# isolated-analog-interface-hw.net
KiCad netlist of a schematic drawn in Altium Designer
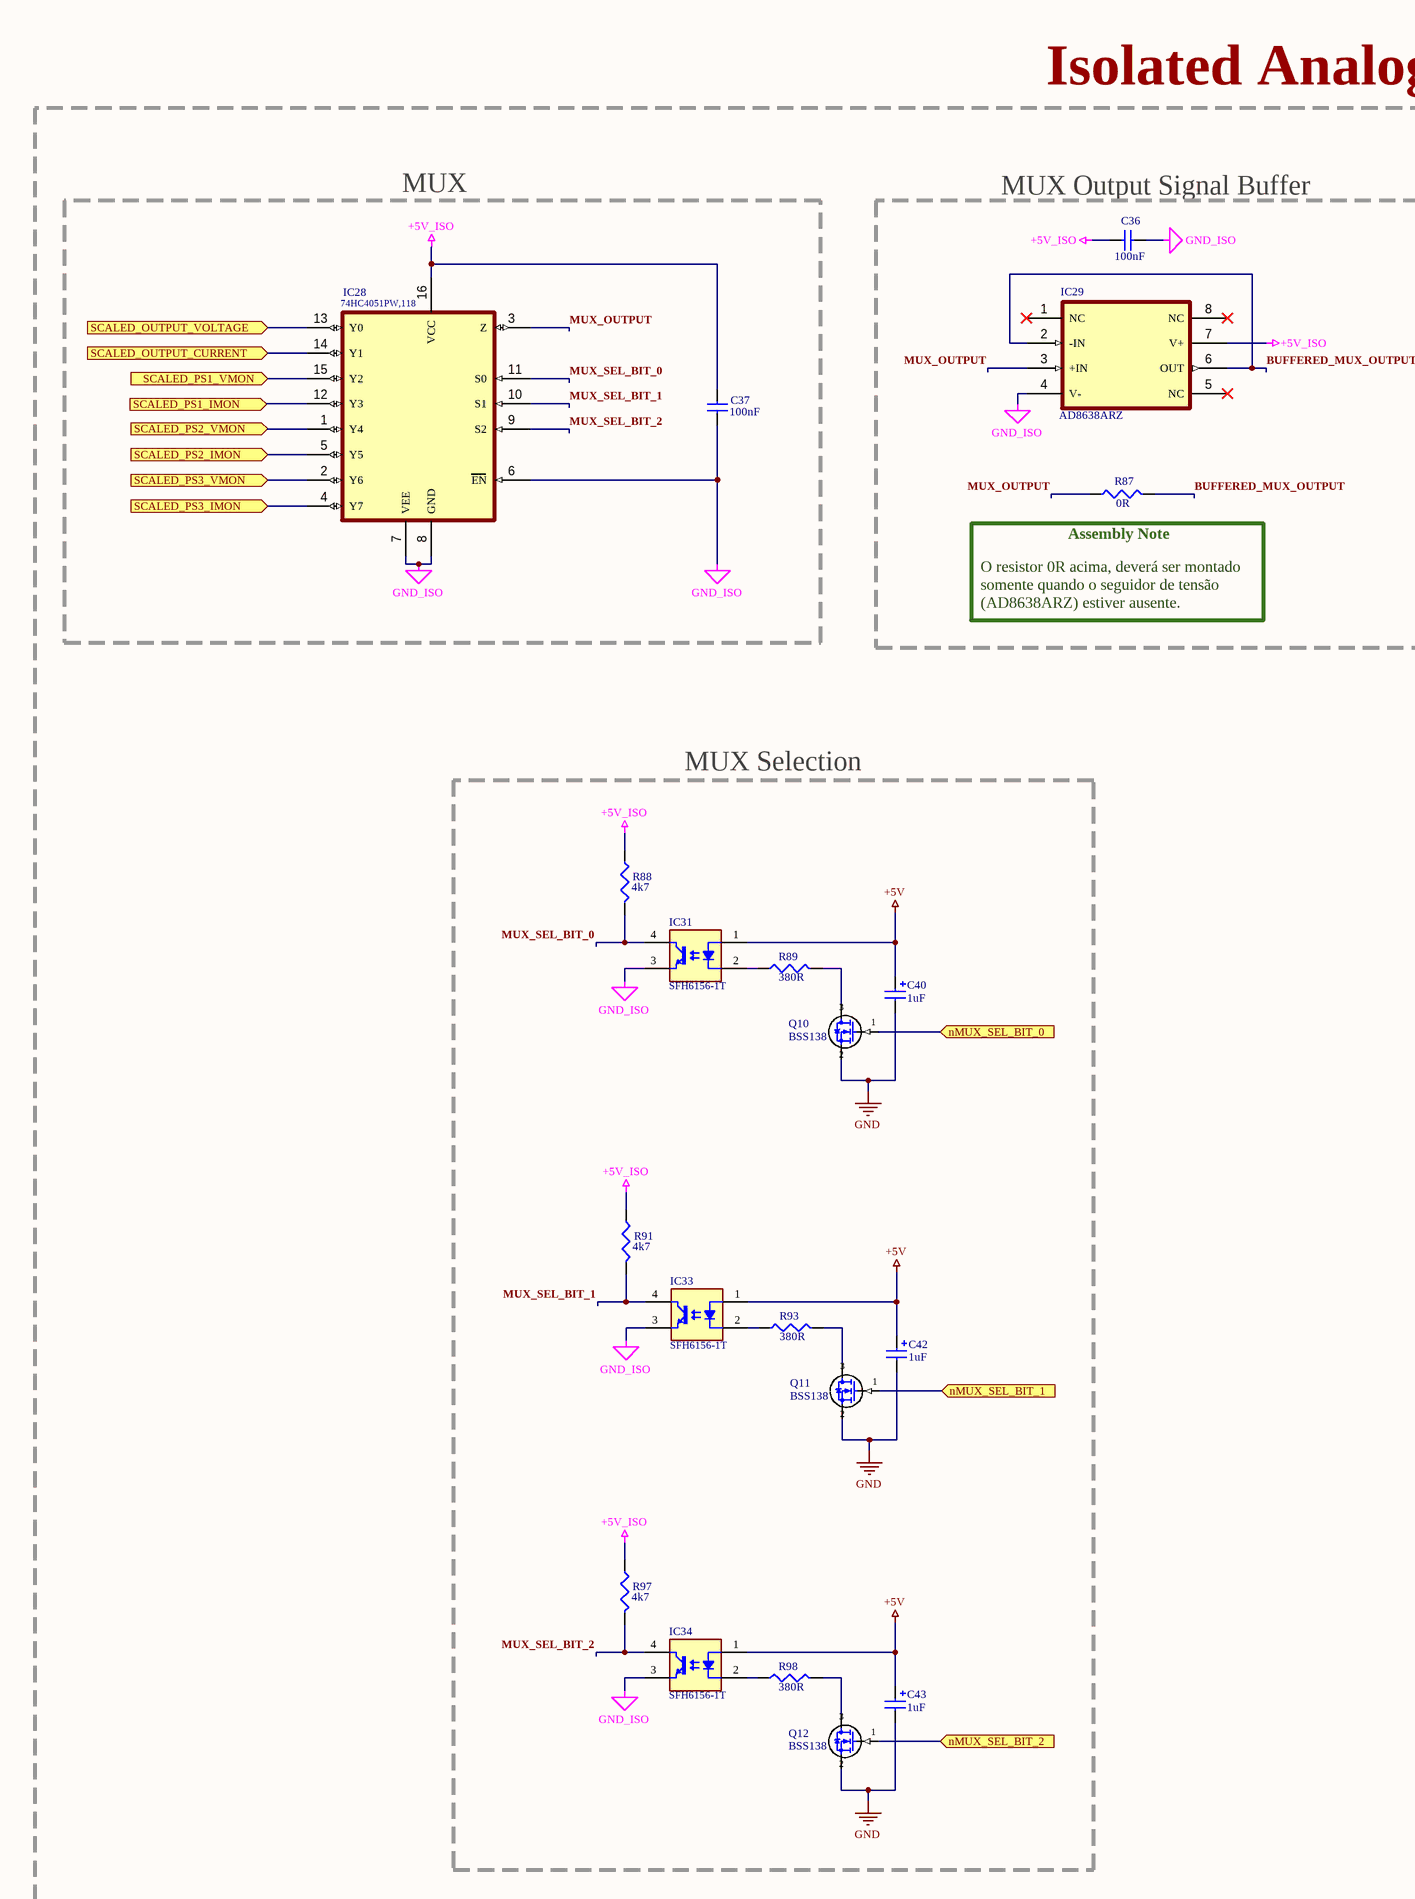
[diagram p0: isolated-analog-interface-hw.SchDoc, left]
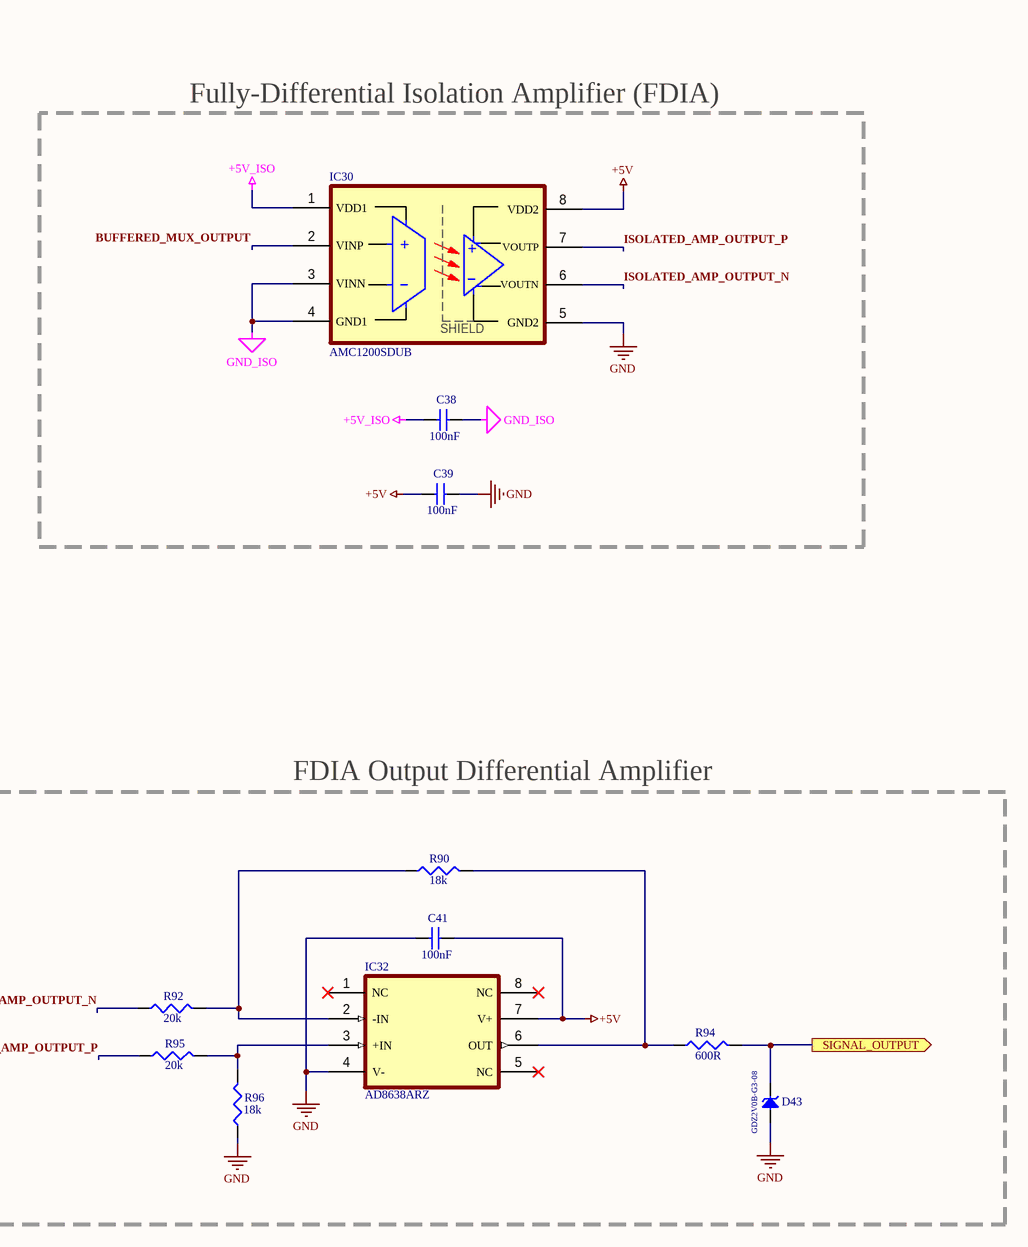
[diagram p1: isolated-analog-interface-hw.SchDoc, right]

(export (version "E")
  (design (tool "Eeschema 10.0.6"))
  (components
    (comp (ref "C36")
      (value "100nF")
      (footprint "C0805")
      (libsource (lib "acopians-powerspy-monitoring-hw-library-schematic") (part "Capacitor 100nF"))
    )
    (comp (ref "C37")
      (value "100nF")
      (footprint "C0805")
      (libsource (lib "acopians-powerspy-monitoring-hw-library-schematic") (part "Capacitor 100nF"))
    )
    (comp (ref "C38")
      (value "100nF")
      (footprint "C0805")
      (libsource (lib "acopians-powerspy-monitoring-hw-library-schematic") (part "Capacitor 100nF"))
    )
    (comp (ref "C39")
      (value "100nF")
      (footprint "C0805")
      (libsource (lib "acopians-powerspy-monitoring-hw-library-schematic") (part "Capacitor 100nF"))
    )
    (comp (ref "C40")
      (value "1uF")
      (footprint "C1206")
      (libsource (lib "acopians-powerspy-monitoring-hw-library-schematic") (part "Capacitor 1uF"))
    )
    (comp (ref "C41")
      (value "100nF")
      (footprint "C0805")
      (libsource (lib "acopians-powerspy-monitoring-hw-library-schematic") (part "Capacitor 100nF"))
    )
    (comp (ref "C42")
      (value "1uF")
      (footprint "C1206")
      (libsource (lib "acopians-powerspy-monitoring-hw-library-schematic") (part "Capacitor 1uF"))
    )
    (comp (ref "C43")
      (value "1uF")
      (footprint "C1206")
      (libsource (lib "acopians-powerspy-monitoring-hw-library-schematic") (part "Capacitor 1uF"))
    )
    (comp (ref "D43")
      (value "GDZ2V0B-G3-08")
      (footprint "SOD-323")
      (libsource (lib "acopians-powerspy-monitoring-hw-library-schematic") (part "Zener GDZ2V0B-G3-08"))
    )
    (comp (ref "IC28")
      (value "74HC4051PW,118")
      (footprint "TSSOP-16")
      (description "8-channel analog multiplexer, TSSOP-16")
      (libsource (lib "acopians-powerspy-monitoring-hw-library-schematic") (part "74HC4051PW,118"))
    )
    (comp (ref "IC29")
      (value "AD8638ARZ")
      (footprint "SOIC-8")
      (description "16V, Auto-Zero, Rail-to-Rail Output Operational Amplifiers")
      (libsource (lib "acopians-powerspy-monitoring-hw-library-schematic") (part "AD8638ARZ"))
    )
    (comp (ref "IC30")
      (value "AMC1200SDUB")
      (footprint "SOP-8")
      (description "Fully-Differential Isolation Amplifier")
      (libsource (lib "acopians-powerspy-monitoring-hw-library-schematic") (part "AMC1200SDUB"))
    )
    (comp (ref "IC31")
      (value "SFH6156-1T")
      (footprint "SMD-4")
      (description "Optocoupler 1 Channel, Phototransistor Output, SMD-4")
      (libsource (lib "acopians-powerspy-monitoring-hw-library-schematic") (part "SFH6156-1T"))
    )
    (comp (ref "IC32")
      (value "AD8638ARZ")
      (footprint "SOIC-8")
      (description "16V, Auto-Zero, Rail-to-Rail Output Operational Amplifiers")
      (libsource (lib "acopians-powerspy-monitoring-hw-library-schematic") (part "AD8638ARZ"))
    )
    (comp (ref "IC33")
      (value "SFH6156-1T")
      (footprint "SMD-4")
      (description "Optocoupler 1 Channel, Phototransistor Output, SMD-4")
      (libsource (lib "acopians-powerspy-monitoring-hw-library-schematic") (part "SFH6156-1T"))
    )
    (comp (ref "IC34")
      (value "SFH6156-1T")
      (footprint "SMD-4")
      (description "Optocoupler 1 Channel, Phototransistor Output, SMD-4")
      (libsource (lib "acopians-powerspy-monitoring-hw-library-schematic") (part "SFH6156-1T"))
    )
    (comp (ref "Q10")
      (value "BSS138")
      (footprint "SOT_23_3")
      (description "MOSFET N-Channel")
      (libsource (lib "acopians-powerspy-monitoring-hw-library-schematic") (part "BSS138"))
    )
    (comp (ref "Q11")
      (value "BSS138")
      (footprint "SOT_23_3")
      (description "MOSFET N-Channel")
      (libsource (lib "acopians-powerspy-monitoring-hw-library-schematic") (part "BSS138"))
    )
    (comp (ref "Q12")
      (value "BSS138")
      (footprint "SOT_23_3")
      (description "MOSFET N-Channel")
      (libsource (lib "acopians-powerspy-monitoring-hw-library-schematic") (part "BSS138"))
    )
    (comp (ref "R87")
      (value "0R")
      (footprint "Resistor 0805")
      (description "Size 0805")
      (libsource (lib "acopians-powerspy-monitoring-hw-library-schematic") (part "Resistor 0R - 0805"))
    )
    (comp (ref "R88")
      (value "4k7")
      (footprint "Resistor 0805")
      (description "Size 0805")
      (libsource (lib "acopians-powerspy-monitoring-hw-library-schematic") (part "Resistor 4k7"))
    )
    (comp (ref "R89")
      (value "380R")
      (footprint "Resistor 0805")
      (description "Size 0805")
      (libsource (lib "acopians-powerspy-monitoring-hw-library-schematic") (part "Resistor 380R"))
    )
    (comp (ref "R90")
      (value "18k")
      (footprint "Resistor 0805")
      (libsource (lib "acopians-powerspy-monitoring-hw-library-schematic") (part "Resistor 18k"))
    )
    (comp (ref "R91")
      (value "4k7")
      (footprint "Resistor 0805")
      (description "Size 0805")
      (libsource (lib "acopians-powerspy-monitoring-hw-library-schematic") (part "Resistor 4k7"))
    )
    (comp (ref "R92")
      (value "20k")
      (footprint "Resistor 0805")
      (libsource (lib "acopians-powerspy-monitoring-hw-library-schematic") (part "Resistor 20k"))
    )
    (comp (ref "R93")
      (value "380R")
      (footprint "Resistor 0805")
      (description "Size 0805")
      (libsource (lib "acopians-powerspy-monitoring-hw-library-schematic") (part "Resistor 380R"))
    )
    (comp (ref "R94")
      (value "600R")
      (footprint "Resistor 0805")
      (libsource (lib "acopians-powerspy-monitoring-hw-library-schematic") (part "Resistor 600R"))
    )
    (comp (ref "R95")
      (value "20k")
      (footprint "Resistor 0805")
      (libsource (lib "acopians-powerspy-monitoring-hw-library-schematic") (part "Resistor 20k"))
    )
    (comp (ref "R96")
      (value "18k")
      (footprint "Resistor 0805")
      (libsource (lib "acopians-powerspy-monitoring-hw-library-schematic") (part "Resistor 18k"))
    )
    (comp (ref "R97")
      (value "4k7")
      (footprint "Resistor 0805")
      (description "Size 0805")
      (libsource (lib "acopians-powerspy-monitoring-hw-library-schematic") (part "Resistor 4k7"))
    )
    (comp (ref "R98")
      (value "380R")
      (footprint "Resistor 0805")
      (description "Size 0805")
      (libsource (lib "acopians-powerspy-monitoring-hw-library-schematic") (part "Resistor 380R"))
    )
  )
  (nets
    (net (code "1") (name "+5V") (class "Default")
      (node (ref "C39") (pin "1") (pinfunction "1_1") (pintype "passive"))
      (node (ref "C40") (pin "1") (pinfunction "1_1") (pintype "passive"))
      (node (ref "C41") (pin "2") (pinfunction "2_2") (pintype "passive"))
      (node (ref "C42") (pin "1") (pinfunction "1_1") (pintype "passive"))
      (node (ref "C43") (pin "1") (pinfunction "1_1") (pintype "passive"))
      (node (ref "IC30") (pin "8") (pinfunction "VDD2_8") (pintype "passive"))
      (node (ref "IC31") (pin "1") (pinfunction "A_1") (pintype "passive"))
      (node (ref "IC32") (pin "7") (pinfunction "V+_7") (pintype "passive"))
      (node (ref "IC33") (pin "1") (pinfunction "A_1") (pintype "passive"))
      (node (ref "IC34") (pin "1") (pinfunction "A_1") (pintype "passive"))
    )
    (net (code "2") (name "+5V_ISO") (class "Default")
      (node (ref "C36") (pin "1") (pinfunction "1_1") (pintype "passive"))
      (node (ref "C37") (pin "1") (pinfunction "1_1") (pintype "passive"))
      (node (ref "C38") (pin "1") (pinfunction "1_1") (pintype "passive"))
      (node (ref "IC28") (pin "16") (pinfunction "VCC_16") (pintype "passive"))
      (node (ref "IC29") (pin "7") (pinfunction "V+_7") (pintype "passive"))
      (node (ref "IC30") (pin "1") (pinfunction "VDD1_1") (pintype "passive"))
      (node (ref "R88") (pin "1") (pinfunction "1_1") (pintype "passive"))
      (node (ref "R91") (pin "1") (pinfunction "1_1") (pintype "passive"))
      (node (ref "R97") (pin "1") (pinfunction "1_1") (pintype "passive"))
    )
    (net (code "3") (name "/BUFFERED_MUX_OUTPUT") (class "Default")
      (node (ref "IC29") (pin "2") (pinfunction "-IN_2") (pintype "input"))
      (node (ref "IC29") (pin "6") (pinfunction "OUT_6") (pintype "output"))
      (node (ref "IC30") (pin "2") (pinfunction "VINP_2") (pintype "passive"))
      (node (ref "R87") (pin "2") (pinfunction "2_2") (pintype "passive"))
    )
    (net (code "4") (name "/ISOLATED_AMP_OUTPUT_N") (class "Default")
      (node (ref "IC30") (pin "6") (pinfunction "VOUTN_6") (pintype "passive"))
      (node (ref "R92") (pin "1") (pinfunction "1_1") (pintype "passive"))
    )
    (net (code "5") (name "/ISOLATED_AMP_OUTPUT_P") (class "Default")
      (node (ref "IC30") (pin "7") (pinfunction "VOUTP_7") (pintype "passive"))
      (node (ref "R95") (pin "1") (pinfunction "1_1") (pintype "passive"))
    )
    (net (code "6") (name "/MUX_OUTPUT") (class "Default")
      (node (ref "IC28") (pin "3") (pinfunction "Z_3") (pintype "bidirectional"))
      (node (ref "IC29") (pin "3") (pinfunction "+IN_3") (pintype "input"))
      (node (ref "R87") (pin "1") (pinfunction "1_1") (pintype "passive"))
    )
    (net (code "7") (name "/MUX_SEL_BIT_0") (class "Default")
      (node (ref "IC28") (pin "11") (pinfunction "S0_11") (pintype "input"))
      (node (ref "IC31") (pin "4") (pinfunction "C_4") (pintype "open_collector"))
      (node (ref "R88") (pin "2") (pinfunction "2_2") (pintype "passive"))
    )
    (net (code "8") (name "/MUX_SEL_BIT_1") (class "Default")
      (node (ref "IC28") (pin "10") (pinfunction "S1_10") (pintype "input"))
      (node (ref "IC33") (pin "4") (pinfunction "C_4") (pintype "open_collector"))
      (node (ref "R91") (pin "2") (pinfunction "2_2") (pintype "passive"))
    )
    (net (code "9") (name "/MUX_SEL_BIT_2") (class "Default")
      (node (ref "IC28") (pin "9") (pinfunction "S2_9") (pintype "input"))
      (node (ref "IC34") (pin "4") (pinfunction "C_4") (pintype "open_collector"))
      (node (ref "R97") (pin "2") (pinfunction "2_2") (pintype "passive"))
    )
    (net (code "10") (name "/SCALED_OUTPUT_CURRENT") (class "Default")
      (node (ref "IC28") (pin "14") (pinfunction "Y1_14") (pintype "bidirectional"))
    )
    (net (code "11") (name "/SCALED_OUTPUT_VOLTAGE") (class "Default")
      (node (ref "IC28") (pin "13") (pinfunction "Y0_13") (pintype "bidirectional"))
    )
    (net (code "12") (name "/SCALED_PS1_IMON") (class "Default")
      (node (ref "IC28") (pin "12") (pinfunction "Y3_12") (pintype "bidirectional"))
    )
    (net (code "13") (name "/SCALED_PS1_VMON") (class "Default")
      (node (ref "IC28") (pin "15") (pinfunction "Y2_15") (pintype "bidirectional"))
    )
    (net (code "14") (name "/SCALED_PS2_IMON") (class "Default")
      (node (ref "IC28") (pin "5") (pinfunction "Y5_5") (pintype "bidirectional"))
    )
    (net (code "15") (name "/SCALED_PS2_VMON") (class "Default")
      (node (ref "IC28") (pin "1") (pinfunction "Y4_1") (pintype "bidirectional"))
    )
    (net (code "16") (name "/SCALED_PS3_IMON") (class "Default")
      (node (ref "IC28") (pin "4") (pinfunction "Y7_4") (pintype "bidirectional"))
    )
    (net (code "17") (name "/SCALED_PS3_VMON") (class "Default")
      (node (ref "IC28") (pin "2") (pinfunction "Y6_2") (pintype "bidirectional"))
    )
    (net (code "18") (name "/SIGNAL_OUTPUT") (class "Default")
      (node (ref "D43") (pin "2") (pintype "passive"))
      (node (ref "R94") (pin "2") (pinfunction "2_2") (pintype "passive"))
    )
    (net (code "19") (name "/nMUX_SEL_BIT_0") (class "Default")
      (node (ref "Q10") (pin "1") (pinfunction "G_1") (pintype "input"))
    )
    (net (code "20") (name "/nMUX_SEL_BIT_1") (class "Default")
      (node (ref "Q11") (pin "1") (pinfunction "G_1") (pintype "input"))
    )
    (net (code "21") (name "/nMUX_SEL_BIT_2") (class "Default")
      (node (ref "Q12") (pin "1") (pinfunction "G_1") (pintype "input"))
    )
    (net (code "22") (name "GND") (class "Default")
      (node (ref "C39") (pin "2") (pinfunction "2_2") (pintype "passive"))
      (node (ref "C40") (pin "2") (pinfunction "2_2") (pintype "passive"))
      (node (ref "C41") (pin "1") (pinfunction "1_1") (pintype "passive"))
      (node (ref "C42") (pin "2") (pinfunction "2_2") (pintype "passive"))
      (node (ref "C43") (pin "2") (pinfunction "2_2") (pintype "passive"))
      (node (ref "D43") (pin "1") (pintype "passive"))
      (node (ref "IC30") (pin "5") (pinfunction "GND2_5") (pintype "passive"))
      (node (ref "IC32") (pin "4") (pinfunction "V-_4") (pintype "passive"))
      (node (ref "Q10") (pin "2") (pinfunction "S_2") (pintype "passive"))
      (node (ref "Q11") (pin "2") (pinfunction "S_2") (pintype "passive"))
      (node (ref "Q12") (pin "2") (pinfunction "S_2") (pintype "passive"))
      (node (ref "R96") (pin "1") (pinfunction "1_1") (pintype "passive"))
    )
    (net (code "23") (name "GND_ISO") (class "Default")
      (node (ref "C36") (pin "2") (pinfunction "2_2") (pintype "passive"))
      (node (ref "C37") (pin "2") (pinfunction "2_2") (pintype "passive"))
      (node (ref "C38") (pin "2") (pinfunction "2_2") (pintype "passive"))
      (node (ref "IC28") (pin "6") (pinfunction "EN_6") (pintype "input"))
      (node (ref "IC28") (pin "7") (pinfunction "VEE_7") (pintype "passive"))
      (node (ref "IC28") (pin "8") (pinfunction "GND_8") (pintype "passive"))
      (node (ref "IC29") (pin "4") (pinfunction "V-_4") (pintype "passive"))
      (node (ref "IC30") (pin "3") (pinfunction "VINN_3") (pintype "passive"))
      (node (ref "IC30") (pin "4") (pinfunction "GND1_4") (pintype "passive"))
      (node (ref "IC31") (pin "3") (pinfunction "E_3") (pintype "open_emitter"))
      (node (ref "IC33") (pin "3") (pinfunction "E_3") (pintype "open_emitter"))
      (node (ref "IC34") (pin "3") (pinfunction "E_3") (pintype "open_emitter"))
    )
    (net (code "24") (name "Net-(IC31-C-Pad2)") (class "Default")
      (node (ref "IC31") (pin "2") (pinfunction "C_2") (pintype "passive"))
      (node (ref "R89") (pin "1") (pinfunction "1_1") (pintype "passive"))
    )
    (net (code "25") (name "Net-(IC32-+IN)") (class "Default")
      (node (ref "IC32") (pin "3") (pinfunction "+IN_3") (pintype "input"))
      (node (ref "R95") (pin "2") (pinfunction "2_2") (pintype "passive"))
      (node (ref "R96") (pin "2") (pinfunction "2_2") (pintype "passive"))
    )
    (net (code "26") (name "Net-(IC32--IN)") (class "Default")
      (node (ref "IC32") (pin "2") (pinfunction "-IN_2") (pintype "input"))
      (node (ref "R90") (pin "1") (pinfunction "1_1") (pintype "passive"))
      (node (ref "R92") (pin "2") (pinfunction "2_2") (pintype "passive"))
    )
    (net (code "27") (name "Net-(IC32-OUT)") (class "Default")
      (node (ref "IC32") (pin "6") (pinfunction "OUT_6") (pintype "output"))
      (node (ref "R90") (pin "2") (pinfunction "2_2") (pintype "passive"))
      (node (ref "R94") (pin "1") (pinfunction "1_1") (pintype "passive"))
    )
    (net (code "28") (name "Net-(IC33-C-Pad2)") (class "Default")
      (node (ref "IC33") (pin "2") (pinfunction "C_2") (pintype "passive"))
      (node (ref "R93") (pin "1") (pinfunction "1_1") (pintype "passive"))
    )
    (net (code "29") (name "Net-(IC34-C-Pad2)") (class "Default")
      (node (ref "IC34") (pin "2") (pinfunction "C_2") (pintype "passive"))
      (node (ref "R98") (pin "1") (pinfunction "1_1") (pintype "passive"))
    )
    (net (code "30") (name "Net-(Q10-D)") (class "Default")
      (node (ref "Q10") (pin "3") (pinfunction "D_3") (pintype "passive"))
      (node (ref "R89") (pin "2") (pinfunction "2_2") (pintype "passive"))
    )
    (net (code "31") (name "Net-(Q11-D)") (class "Default")
      (node (ref "Q11") (pin "3") (pinfunction "D_3") (pintype "passive"))
      (node (ref "R93") (pin "2") (pinfunction "2_2") (pintype "passive"))
    )
    (net (code "32") (name "Net-(Q12-D)") (class "Default")
      (node (ref "Q12") (pin "3") (pinfunction "D_3") (pintype "passive"))
      (node (ref "R98") (pin "2") (pinfunction "2_2") (pintype "passive"))
    )
    (net (code "33") (name "unconnected-(IC29-NC-Pad1)") (class "Default")
      (node (ref "IC29") (pin "1") (pinfunction "NC_1") (pintype "passive+no_connect"))
    )
    (net (code "34") (name "unconnected-(IC29-NC-Pad5)") (class "Default")
      (node (ref "IC29") (pin "5") (pinfunction "NC_5") (pintype "passive+no_connect"))
    )
    (net (code "35") (name "unconnected-(IC29-NC-Pad8)") (class "Default")
      (node (ref "IC29") (pin "8") (pinfunction "NC_8") (pintype "passive+no_connect"))
    )
    (net (code "36") (name "unconnected-(IC32-NC-Pad1)") (class "Default")
      (node (ref "IC32") (pin "1") (pinfunction "NC_1") (pintype "passive+no_connect"))
    )
    (net (code "37") (name "unconnected-(IC32-NC-Pad5)") (class "Default")
      (node (ref "IC32") (pin "5") (pinfunction "NC_5") (pintype "passive+no_connect"))
    )
    (net (code "38") (name "unconnected-(IC32-NC-Pad8)") (class "Default")
      (node (ref "IC32") (pin "8") (pinfunction "NC_8") (pintype "passive+no_connect"))
    )
  )
)
